# LB_BIT_o1_LED-v02_rev1.net
KiCad netlist of a schematic drawn in EAGLE
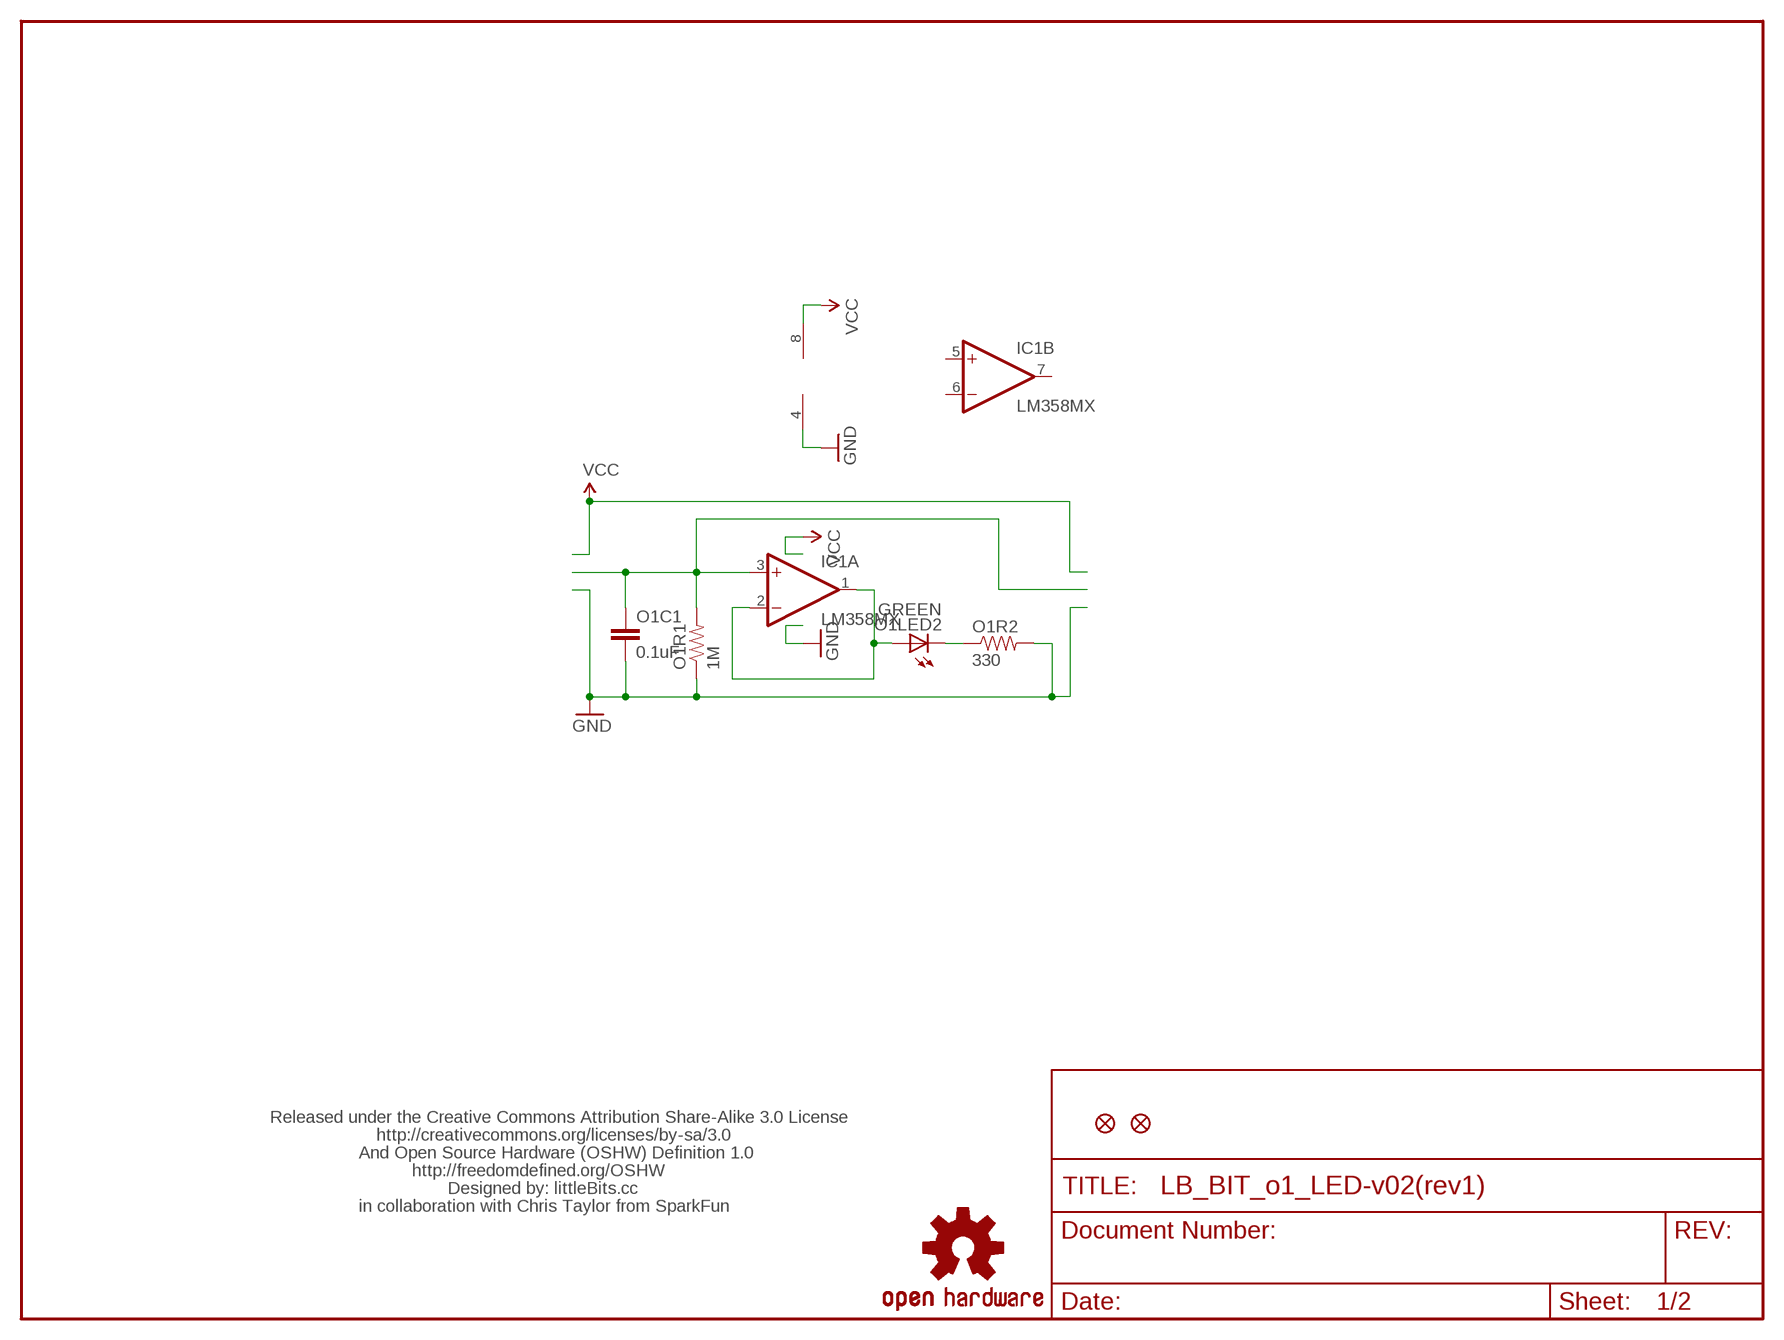
[diagram p0: schematic, sheet 1]
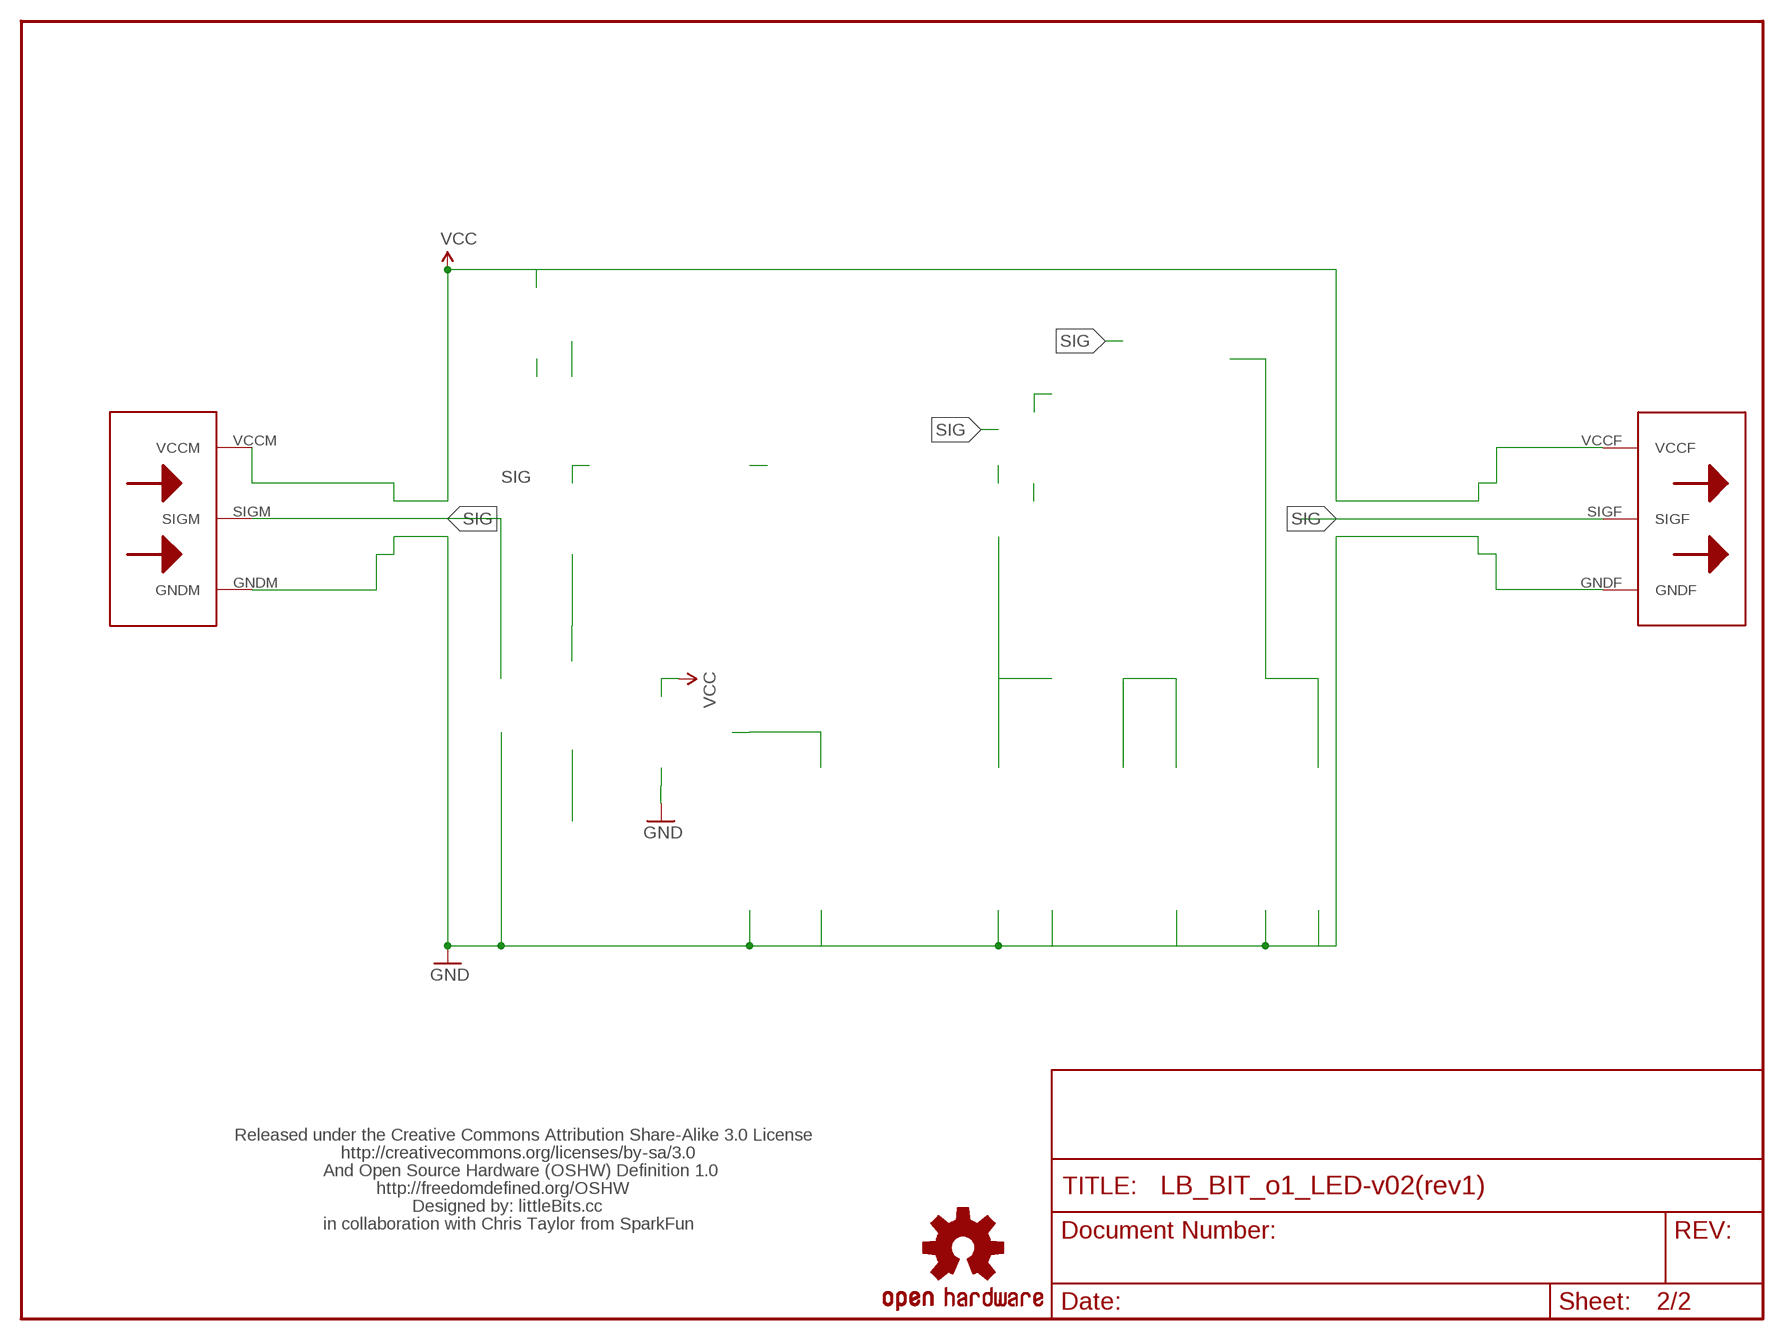
[diagram p1: schematic, sheet 2]

(export (version "E")
  (design (tool "Eeschema 10.0.6"))
  (components
    (comp (ref "U$2")
      (value "OSHW-LOGOL")
      (footprint "eagle-import:OSHW-LOGO-L")
      (libsource (lib "eagle-import") (part "OSHW-LOGOL"))
    )
    (comp (ref "U$4")
      (value "LB_CREDITS")
      (footprint "eagle-import:OSHWCREDIT")
      (libsource (lib "eagle-import") (part "LB_CREDITS"))
    )
    (comp (ref "U$8")
      (value "BIGBIT")
      (footprint "eagle-import:BIGBIT")
      (libsource (lib "eagle-import") (part "BIGBIT"))
    )
    (comp (ref "IC1")
      (value "LM358MX")
      (footprint "eagle-import:SO08")
      (libsource (lib "eagle-import") (part "LM358MX"))
    )
    (comp (ref "JP1")
      (value "FIDUCIAL1X2.5")
      (footprint "eagle-import:FIDUCIAL-1X2.5")
      (libsource (lib "eagle-import") (part "FIDUCIAL1X2.5"))
    )
    (comp (ref "JP2")
      (value "FIDUCIAL1X2.5")
      (footprint "eagle-import:FIDUCIAL-1X2.5")
      (libsource (lib "eagle-import") (part "FIDUCIAL1X2.5"))
    )
    (comp (ref "O1C1")
      (value "0.1uF")
      (footprint "eagle-import:1206")
      (libsource (lib "eagle-import") (part "CAP1206"))
    )
    (comp (ref "O1LED2")
      (value "GREEN")
      (footprint "eagle-import:LED-1206")
      (libsource (lib "eagle-import") (part "LED1206"))
    )
    (comp (ref "O1R1")
      (value "1M")
      (footprint "eagle-import:0805")
      (libsource (lib "eagle-import") (part "RESISTOR"))
    )
    (comp (ref "O1R2")
      (value "330")
      (footprint "eagle-import:0805")
      (libsource (lib "eagle-import") (part "RESISTOR"))
    )
    (comp (ref "U$1")
      (value "LB_CREDITS")
      (footprint "eagle-import:OSHWCREDIT")
      (libsource (lib "eagle-import") (part "LB_CREDITS"))
    )
    (comp (ref "U$3")
      (value "OSHW-LOGOL")
      (footprint "eagle-import:OSHW-LOGO-L")
      (libsource (lib "eagle-import") (part "OSHW-LOGOL"))
    )
  )
  (nets
    (net (code "1") (name "GND") (class "Default")
      (node (ref "IC1") (pin "4") (pinfunction "V-_4") (pintype "power_in"))
      (node (ref "O1C1") (pin "2") (pinfunction "2_2") (pintype "passive"))
      (node (ref "O1R1") (pin "1") (pinfunction "1_1") (pintype "passive"))
      (node (ref "O1R2") (pin "2") (pinfunction "2_2") (pintype "passive"))
      (node (ref "U$8") (pin "GNDF") (pinfunction "GNDF_GNDF") (pintype "bidirectional"))
      (node (ref "U$8") (pin "GNDM") (pinfunction "GNDM_GNDM") (pintype "bidirectional"))
    )
    (net (code "2") (name "Net-(IC1A--IN)") (class "Default")
      (node (ref "IC1") (pin "1") (pinfunction "OUT_1") (pintype "output"))
      (node (ref "IC1") (pin "2") (pinfunction "-IN_2") (pintype "input"))
      (node (ref "O1LED2") (pin "A") (pinfunction "A_A") (pintype "passive"))
    )
    (net (code "3") (name "Net-(O1LED2-PadC)") (class "Default")
      (node (ref "O1LED2") (pin "C") (pinfunction "C_C") (pintype "passive"))
      (node (ref "O1R2") (pin "1") (pinfunction "1_1") (pintype "passive"))
    )
    (net (code "4") (name "SIG") (class "Default")
      (node (ref "IC1") (pin "3") (pinfunction "+IN_3") (pintype "input"))
      (node (ref "O1C1") (pin "1") (pinfunction "1_1") (pintype "passive"))
      (node (ref "O1R1") (pin "2") (pinfunction "2_2") (pintype "passive"))
      (node (ref "U$8") (pin "SIGF") (pinfunction "SIGF_SIGF") (pintype "bidirectional"))
      (node (ref "U$8") (pin "SIGM") (pinfunction "SIGM_SIGM") (pintype "bidirectional"))
    )
    (net (code "5") (name "VCC") (class "Default")
      (node (ref "IC1") (pin "8") (pinfunction "V+_8") (pintype "power_in"))
      (node (ref "U$8") (pin "VCCF") (pinfunction "VCCF_VCCF") (pintype "bidirectional"))
      (node (ref "U$8") (pin "VCCM") (pinfunction "VCCM_VCCM") (pintype "bidirectional"))
    )
    (net (code "6") (name "unconnected-(IC1B-+IN-Pad5)") (class "Default")
      (node (ref "IC1") (pin "5") (pinfunction "+IN_5") (pintype "input"))
    )
    (net (code "7") (name "unconnected-(IC1B--IN-Pad6)") (class "Default")
      (node (ref "IC1") (pin "6") (pinfunction "-IN_6") (pintype "input"))
    )
    (net (code "8") (name "unconnected-(IC1B-OUT-Pad7)") (class "Default")
      (node (ref "IC1") (pin "7") (pinfunction "OUT_7") (pintype "output"))
    )
  )
)
